# fcu.net
KiCad netlist of a schematic drawn in Altium Designer
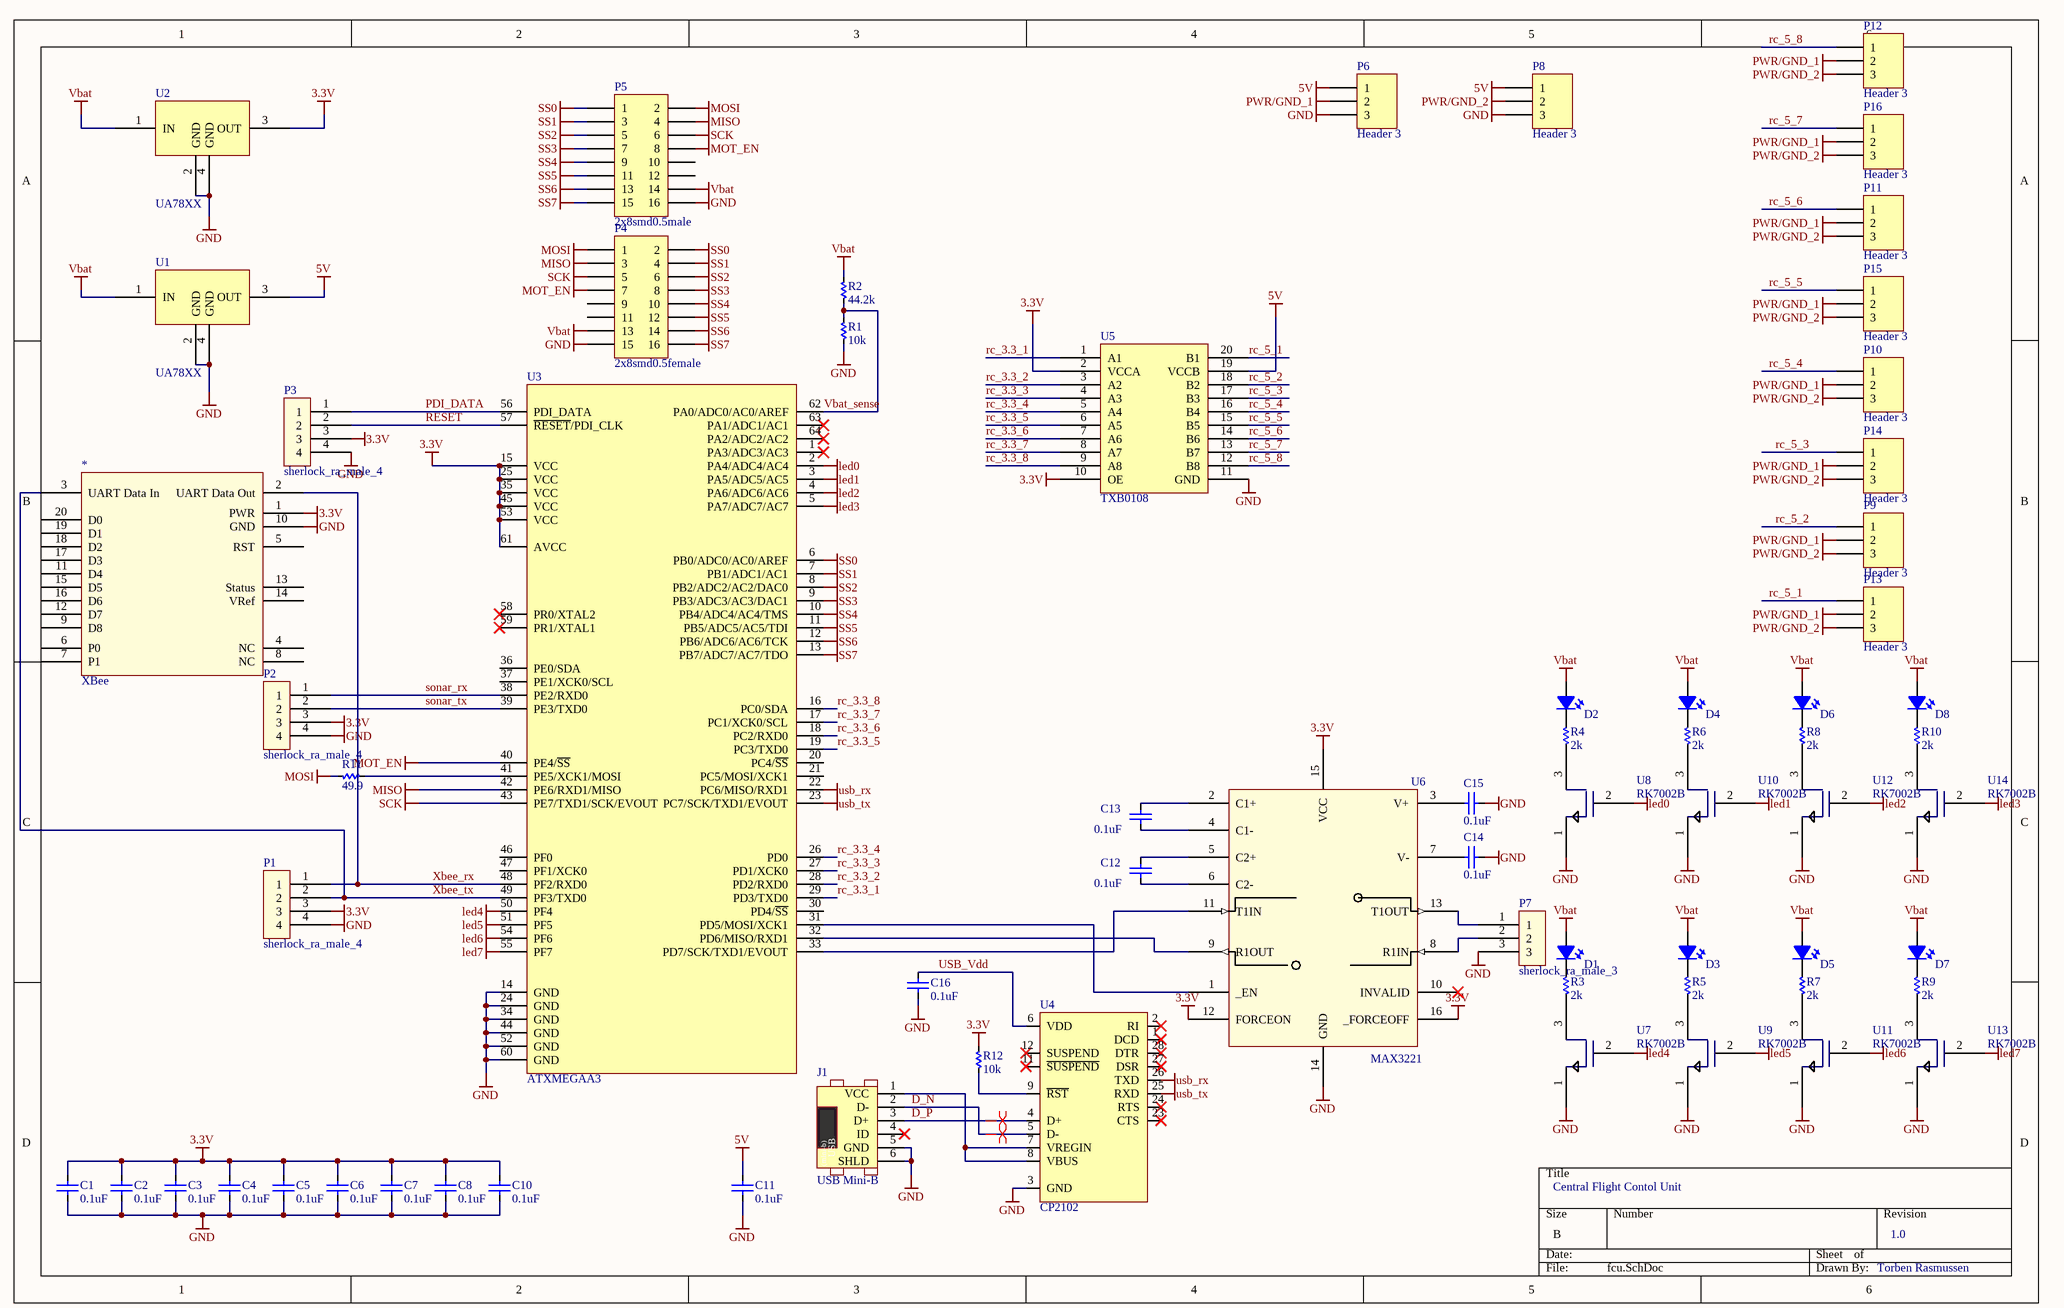
[diagram p0: fcu.SchDoc]

(export (version "E")
  (design (tool "Eeschema 10.0.6"))
  (components
    (comp (ref "*") (value "XBee") (footprint "XBee") (libsource (lib "fcu") (part "XBee")))
    (comp (ref "C1")
      (value "0.1uF")
      (footprint "0603 (1608) RECT")
      (fields
        (field (name "MANUFACTURER") "Murata")
        (field (name "PART NO.") "GRM188xxxxxxxxx")
        (field (name "Comment") "Capacitor")
      )
      (libsource (lib "SMT Chip") (part "Capacitor"))
    )
    (comp (ref "C2")
      (value "0.1uF")
      (footprint "0603 (1608) RECT")
      (fields
        (field (name "MANUFACTURER") "Murata")
        (field (name "PART NO.") "GRM188xxxxxxxxx")
        (field (name "Comment") "Capacitor")
      )
      (libsource (lib "SMT Chip") (part "Capacitor"))
    )
    (comp (ref "C3")
      (value "0.1uF")
      (footprint "0603 (1608) RECT")
      (fields
        (field (name "MANUFACTURER") "Murata")
        (field (name "PART NO.") "GRM188xxxxxxxxx")
        (field (name "Comment") "Capacitor")
      )
      (libsource (lib "SMT Chip") (part "Capacitor"))
    )
    (comp (ref "C4")
      (value "0.1uF")
      (footprint "0603 (1608) RECT")
      (fields
        (field (name "MANUFACTURER") "Murata")
        (field (name "PART NO.") "GRM188xxxxxxxxx")
        (field (name "Comment") "Capacitor")
      )
      (libsource (lib "SMT Chip") (part "Capacitor"))
    )
    (comp (ref "C5")
      (value "0.1uF")
      (footprint "0603 (1608) RECT")
      (fields
        (field (name "MANUFACTURER") "Murata")
        (field (name "PART NO.") "GRM188xxxxxxxxx")
        (field (name "Comment") "Capacitor")
      )
      (libsource (lib "SMT Chip") (part "Capacitor"))
    )
    (comp (ref "C6")
      (value "0.1uF")
      (footprint "0603 (1608) RECT")
      (fields
        (field (name "MANUFACTURER") "Murata")
        (field (name "PART NO.") "GRM188xxxxxxxxx")
        (field (name "Comment") "Capacitor")
      )
      (libsource (lib "SMT Chip") (part "Capacitor"))
    )
    (comp (ref "C7")
      (value "0.1uF")
      (footprint "0603 (1608) RECT")
      (fields
        (field (name "MANUFACTURER") "Murata")
        (field (name "PART NO.") "GRM188xxxxxxxxx")
        (field (name "Comment") "Capacitor")
      )
      (libsource (lib "SMT Chip") (part "Capacitor"))
    )
    (comp (ref "C8")
      (value "0.1uF")
      (footprint "0603 (1608) RECT")
      (fields
        (field (name "MANUFACTURER") "Murata")
        (field (name "PART NO.") "GRM188xxxxxxxxx")
        (field (name "Comment") "Capacitor")
      )
      (libsource (lib "SMT Chip") (part "Capacitor"))
    )
    (comp (ref "C10")
      (value "0.1uF")
      (footprint "0603 (1608) RECT")
      (fields
        (field (name "MANUFACTURER") "Murata")
        (field (name "PART NO.") "GRM188xxxxxxxxx")
        (field (name "Comment") "Capacitor")
      )
      (libsource (lib "SMT Chip") (part "Capacitor"))
    )
    (comp (ref "C11")
      (value "0.1uF")
      (footprint "0603 (1608) RECT")
      (fields
        (field (name "MANUFACTURER") "Murata")
        (field (name "PART NO.") "GRM188xxxxxxxxx")
        (field (name "Comment") "Capacitor")
      )
      (libsource (lib "SMT Chip") (part "Capacitor"))
    )
    (comp (ref "C12")
      (value "0.1uF")
      (footprint "0603 (1608) RECT")
      (fields
        (field (name "MANUFACTURER") "Murata")
        (field (name "PART NO.") "GRM188xxxxxxxxx")
        (field (name "Comment") "Capacitor")
      )
      (libsource (lib "SMT Chip") (part "Capacitor"))
    )
    (comp (ref "C13")
      (value "0.1uF")
      (footprint "0603 (1608) RECT")
      (fields
        (field (name "MANUFACTURER") "Murata")
        (field (name "PART NO.") "GRM188xxxxxxxxx")
        (field (name "Comment") "Capacitor")
      )
      (libsource (lib "SMT Chip") (part "Capacitor"))
    )
    (comp (ref "C14")
      (value "0.1uF")
      (footprint "0603 (1608) RECT")
      (fields
        (field (name "MANUFACTURER") "Murata")
        (field (name "PART NO.") "GRM188xxxxxxxxx")
        (field (name "Comment") "Capacitor")
      )
      (libsource (lib "SMT Chip") (part "Capacitor"))
    )
    (comp (ref "C15")
      (value "0.1uF")
      (footprint "0603 (1608) RECT")
      (fields
        (field (name "MANUFACTURER") "Murata")
        (field (name "PART NO.") "GRM188xxxxxxxxx")
        (field (name "Comment") "Capacitor")
      )
      (libsource (lib "SMT Chip") (part "Capacitor"))
    )
    (comp (ref "C16")
      (value "0.1uF")
      (footprint "0603 (1608) RECT")
      (fields
        (field (name "MANUFACTURER") "Murata")
        (field (name "PART NO.") "GRM188xxxxxxxxx")
        (field (name "Comment") "Capacitor")
      )
      (libsource (lib "SMT Chip") (part "Capacitor"))
    )
    (comp (ref "D1")
      (value "LED")
      (footprint "LED 0603 (1608)")
      (fields (field (name "PART NO.") "LTST-C170XXX") (field (name "MANUFACTURER") "Lite-On"))
      (libsource (lib "Diode") (part "LED"))
    )
    (comp (ref "D2")
      (value "LED")
      (footprint "LED 0603 (1608)")
      (fields (field (name "PART NO.") "LTST-C170XXX") (field (name "MANUFACTURER") "Lite-On"))
      (libsource (lib "Diode") (part "LED"))
    )
    (comp (ref "D3")
      (value "LED")
      (footprint "LED 0603 (1608)")
      (fields (field (name "PART NO.") "LTST-C170XXX") (field (name "MANUFACTURER") "Lite-On"))
      (libsource (lib "Diode") (part "LED"))
    )
    (comp (ref "D4")
      (value "LED")
      (footprint "LED 0603 (1608)")
      (fields (field (name "PART NO.") "LTST-C170XXX") (field (name "MANUFACTURER") "Lite-On"))
      (libsource (lib "Diode") (part "LED"))
    )
    (comp (ref "D5")
      (value "LED")
      (footprint "LED 0603 (1608)")
      (fields (field (name "PART NO.") "LTST-C170XXX") (field (name "MANUFACTURER") "Lite-On"))
      (libsource (lib "Diode") (part "LED"))
    )
    (comp (ref "D6")
      (value "LED")
      (footprint "LED 0603 (1608)")
      (fields (field (name "PART NO.") "LTST-C170XXX") (field (name "MANUFACTURER") "Lite-On"))
      (libsource (lib "Diode") (part "LED"))
    )
    (comp (ref "D7")
      (value "LED")
      (footprint "LED 0603 (1608)")
      (fields (field (name "PART NO.") "LTST-C170XXX") (field (name "MANUFACTURER") "Lite-On"))
      (libsource (lib "Diode") (part "LED"))
    )
    (comp (ref "D8")
      (value "LED")
      (footprint "LED 0603 (1608)")
      (fields (field (name "PART NO.") "LTST-C170XXX") (field (name "MANUFACTURER") "Lite-On"))
      (libsource (lib "Diode") (part "LED"))
    )
    (comp (ref "J1")
      (value "USB Mini-B")
      (footprint "USB MINI-B (PCB TAB)")
      (fields (field (name "PART NO.") "54819-0572") (field (name "MANUFACTURER") "Molex"))
      (libsource (lib "USB") (part "USB Mini-B"))
    )
    (comp (ref "P1")
      (value "sherlock_ra_male_4")
      (footprint "sherlock_ra_male_4")
      (libsource (lib "fcu") (part "sherlock_ra_male_4"))
    )
    (comp (ref "P2")
      (value "sherlock_ra_male_4")
      (footprint "sherlock_ra_male_4")
      (libsource (lib "fcu") (part "sherlock_ra_male_4"))
    )
    (comp (ref "P3")
      (value "sherlock_ra_male_4")
      (footprint "sherlock_ra_male_4")
      (libsource (lib "fcu") (part "sherlock_ra_male_4"))
    )
    (comp (ref "P4")
      (value "2x8smd0.5female")
      (footprint "S9007E-08-ND")
      (fields (field (name "PART NO.") "S9007E-08-ND"))
      (libsource (lib "falcon_mcu") (part "2x8smd0.5female"))
    )
    (comp (ref "P5")
      (value "2x8smd0.5male")
      (footprint "S9007E-08-ND-noholes")
      (fields (field (name "PART NO.") "S9013E-08-ND"))
      (libsource (lib "falcon_mcu") (part "2x8smd0.5male"))
    )
    (comp (ref "P6")
      (value "Header 3")
      (footprint "HDR1X3")
      (description "Header, 3-Pin")
      (fields (field (name "PUBLISHER") "Altium Limited"))
      (libsource (lib "Miscellaneous Connectors") (part "Header 3"))
    )
    (comp (ref "P7")
      (value "sherlock_ra_male_3")
      (footprint "sherlock_ra_male_3")
      (libsource (lib "fcu") (part "sherlock_ra_male_3"))
    )
    (comp (ref "P8")
      (value "Header 3")
      (footprint "HDR1X3")
      (description "Header, 3-Pin")
      (fields (field (name "PUBLISHER") "Altium Limited"))
      (libsource (lib "Miscellaneous Connectors") (part "Header 3"))
    )
    (comp (ref "P9")
      (value "Header 3")
      (footprint "HDR1X3")
      (description "Header, 3-Pin")
      (fields (field (name "PUBLISHER") "Altium Limited"))
      (libsource (lib "Miscellaneous Connectors") (part "Header 3"))
    )
    (comp (ref "P10")
      (value "Header 3")
      (footprint "HDR1X3")
      (description "Header, 3-Pin")
      (fields (field (name "PUBLISHER") "Altium Limited"))
      (libsource (lib "Miscellaneous Connectors") (part "Header 3"))
    )
    (comp (ref "P11")
      (value "Header 3")
      (footprint "HDR1X3")
      (description "Header, 3-Pin")
      (fields (field (name "PUBLISHER") "Altium Limited"))
      (libsource (lib "Miscellaneous Connectors") (part "Header 3"))
    )
    (comp (ref "P12")
      (value "Header 3")
      (footprint "HDR1X3")
      (description "Header, 3-Pin")
      (fields (field (name "PUBLISHER") "Altium Limited"))
      (libsource (lib "Miscellaneous Connectors") (part "Header 3"))
    )
    (comp (ref "P13")
      (value "Header 3")
      (footprint "HDR1X3")
      (description "Header, 3-Pin")
      (fields (field (name "PUBLISHER") "Altium Limited"))
      (libsource (lib "Miscellaneous Connectors") (part "Header 3"))
    )
    (comp (ref "P14")
      (value "Header 3")
      (footprint "HDR1X3")
      (description "Header, 3-Pin")
      (fields (field (name "PUBLISHER") "Altium Limited"))
      (libsource (lib "Miscellaneous Connectors") (part "Header 3"))
    )
    (comp (ref "P15")
      (value "Header 3")
      (footprint "HDR1X3")
      (description "Header, 3-Pin")
      (fields (field (name "PUBLISHER") "Altium Limited"))
      (libsource (lib "Miscellaneous Connectors") (part "Header 3"))
    )
    (comp (ref "P16")
      (value "Header 3")
      (footprint "HDR1X3")
      (description "Header, 3-Pin")
      (fields (field (name "PUBLISHER") "Altium Limited"))
      (libsource (lib "Miscellaneous Connectors") (part "Header 3"))
    )
    (comp (ref "R1")
      (value "10k")
      (footprint "0603 (1608) BRACKET")
      (description "Resistor")
      (fields
        (field (name "PART NO.") "CRCW06031K00xxxxxxxxxx")
        (field (name "MANUFACTURER") "Vishay / Dale")
      )
      (libsource (lib "SMT Chip") (part "Resistor"))
    )
    (comp (ref "R2")
      (value "44.2k")
      (footprint "0603 (1608) BRACKET")
      (description "Resistor")
      (fields
        (field (name "PART NO.") "CRCW06031K00xxxxxxxxxx")
        (field (name "MANUFACTURER") "Vishay / Dale")
      )
      (libsource (lib "SMT Chip") (part "Resistor"))
    )
    (comp (ref "R3")
      (value "2k")
      (footprint "0603 (1608) BRACKET")
      (description "Resistor")
      (fields
        (field (name "PART NO.") "CRCW06031K00xxxxxxxxxx")
        (field (name "MANUFACTURER") "Vishay / Dale")
      )
      (libsource (lib "SMT Chip") (part "Resistor"))
    )
    (comp (ref "R4")
      (value "2k")
      (footprint "0603 (1608) BRACKET")
      (description "Resistor")
      (fields
        (field (name "PART NO.") "CRCW06031K00xxxxxxxxxx")
        (field (name "MANUFACTURER") "Vishay / Dale")
      )
      (libsource (lib "SMT Chip") (part "Resistor"))
    )
    (comp (ref "R5")
      (value "2k")
      (footprint "0603 (1608) BRACKET")
      (description "Resistor")
      (fields
        (field (name "PART NO.") "CRCW06031K00xxxxxxxxxx")
        (field (name "MANUFACTURER") "Vishay / Dale")
      )
      (libsource (lib "SMT Chip") (part "Resistor"))
    )
    (comp (ref "R6")
      (value "2k")
      (footprint "0603 (1608) BRACKET")
      (description "Resistor")
      (fields
        (field (name "PART NO.") "CRCW06031K00xxxxxxxxxx")
        (field (name "MANUFACTURER") "Vishay / Dale")
      )
      (libsource (lib "SMT Chip") (part "Resistor"))
    )
    (comp (ref "R7")
      (value "2k")
      (footprint "0603 (1608) BRACKET")
      (description "Resistor")
      (fields
        (field (name "PART NO.") "CRCW06031K00xxxxxxxxxx")
        (field (name "MANUFACTURER") "Vishay / Dale")
      )
      (libsource (lib "SMT Chip") (part "Resistor"))
    )
    (comp (ref "R8")
      (value "2k")
      (footprint "0603 (1608) BRACKET")
      (description "Resistor")
      (fields
        (field (name "PART NO.") "CRCW06031K00xxxxxxxxxx")
        (field (name "MANUFACTURER") "Vishay / Dale")
      )
      (libsource (lib "SMT Chip") (part "Resistor"))
    )
    (comp (ref "R9")
      (value "2k")
      (footprint "0603 (1608) BRACKET")
      (description "Resistor")
      (fields
        (field (name "PART NO.") "CRCW06031K00xxxxxxxxxx")
        (field (name "MANUFACTURER") "Vishay / Dale")
      )
      (libsource (lib "SMT Chip") (part "Resistor"))
    )
    (comp (ref "R10")
      (value "2k")
      (footprint "0603 (1608) BRACKET")
      (description "Resistor")
      (fields
        (field (name "PART NO.") "CRCW06031K00xxxxxxxxxx")
        (field (name "MANUFACTURER") "Vishay / Dale")
      )
      (libsource (lib "SMT Chip") (part "Resistor"))
    )
    (comp (ref "R11")
      (value "49.9")
      (footprint "0603 (1608) BRACKET")
      (description "Resistor")
      (fields
        (field (name "PART NO.") "CRCW06031K00xxxxxxxxxx")
        (field (name "MANUFACTURER") "Vishay / Dale")
      )
      (libsource (lib "SMT Chip") (part "Resistor"))
    )
    (comp (ref "R12")
      (value "10k")
      (footprint "0603 (1608) BRACKET")
      (description "Resistor")
      (fields
        (field (name "PART NO.") "CRCW06031K00xxxxxxxxxx")
        (field (name "MANUFACTURER") "Vishay / Dale")
      )
      (libsource (lib "SMT Chip") (part "Resistor"))
    )
    (comp (ref "U1") (value "UA78XX") (footprint "SOT-223") (libsource (lib "fcu") (part "UA78XX")))
    (comp (ref "U2") (value "UA78XX") (footprint "SOT-223") (libsource (lib "fcu") (part "UA78XX")))
    (comp (ref "U3")
      (value "ATXMEGAA3")
      (footprint "QFN-64")
      (fields (field (name "MANUFACTURER") "Atmel") (field (name "PART NO.") "ATXMEGA128A3"))
      (libsource (lib "XMEGA") (part "ATXMEGAA3"))
    )
    (comp (ref "U4")
      (value "CP2102")
      (footprint "QFN28 5x5 SILABS")
      (fields (field (name "MANUFACTURER") "Silicon Labs"))
      (libsource (lib "CP2102") (part "CP2102"))
    )
    (comp (ref "U5")
      (value "TXB0108")
      (footprint "falcon:TSSOP-20")
      (fields (field (name "MANUFACTURER") "Texas Instruments"))
      (libsource (lib "TXB0108") (part "TXB0108"))
    )
    (comp (ref "U6") (value "MAX3221") (footprint "TSSOP-16") (libsource (lib "fcu") (part "MAX3221")))
    (comp (ref "U7") (value "RK7002B") (footprint "SOT-23-RK7002B") (libsource (lib "fcu") (part "RK7002B")))
    (comp (ref "U8") (value "RK7002B") (footprint "SOT-23-RK7002B") (libsource (lib "fcu") (part "RK7002B")))
    (comp (ref "U9") (value "RK7002B") (footprint "SOT-23-RK7002B") (libsource (lib "fcu") (part "RK7002B")))
    (comp (ref "U10") (value "RK7002B") (footprint "SOT-23-RK7002B") (libsource (lib "fcu") (part "RK7002B")))
    (comp (ref "U11") (value "RK7002B") (footprint "SOT-23-RK7002B") (libsource (lib "fcu") (part "RK7002B")))
    (comp (ref "U12") (value "RK7002B") (footprint "SOT-23-RK7002B") (libsource (lib "fcu") (part "RK7002B")))
    (comp (ref "U13") (value "RK7002B") (footprint "SOT-23-RK7002B") (libsource (lib "fcu") (part "RK7002B")))
    (comp (ref "U14") (value "RK7002B") (footprint "SOT-23-RK7002B") (libsource (lib "fcu") (part "RK7002B")))
  )
  (nets
    (net (code "1") (name "/D_N") (class "Default")
      (node (ref "J1") (pin "2") (pinfunction "D-_2") (pintype "passive"))
      (node (ref "U4") (pin "5") (pinfunction "D-_5") (pintype "passive"))
    )
    (net (code "2") (name "/D_P") (class "Default")
      (node (ref "J1") (pin "3") (pinfunction "D+_3") (pintype "passive"))
      (node (ref "U4") (pin "4") (pinfunction "D+_4") (pintype "passive"))
    )
    (net (code "3") (name "/PDI_DATA") (class "Default")
      (node (ref "P3") (pin "1") (pinfunction "1_1") (pintype "passive"))
      (node (ref "U3") (pin "56") (pinfunction "PDI_DATA_56") (pintype "passive"))
    )
    (net (code "4") (name "/RESET") (class "Default")
      (node (ref "P3") (pin "2") (pinfunction "2_2") (pintype "passive"))
      (node (ref "U3") (pin "57") (pinfunction "~{RESET}/PDI_CLK_57") (pintype "passive"))
    )
    (net (code "5") (name "/USB_Vdd") (class "Default")
      (node (ref "C16") (pin "1") (pinfunction "1_1") (pintype "passive"))
      (node (ref "U4") (pin "6") (pinfunction "VDD_6") (pintype "passive"))
    )
    (net (code "6") (name "/Vbat_sense") (class "Default")
      (node (ref "R1") (pin "2") (pinfunction "2_2") (pintype "passive"))
      (node (ref "R2") (pin "1") (pinfunction "1_1") (pintype "passive"))
      (node (ref "U3") (pin "62") (pinfunction "PA0/ADC0/AC0/AREF_62") (pintype "passive"))
    )
    (net (code "7") (name "/Xbee_rx") (class "Default")
      (node (ref "*") (pin "2") (pinfunction "UART_Data_Out_2") (pintype "passive"))
      (node (ref "P1") (pin "1") (pinfunction "1_1") (pintype "passive"))
      (node (ref "U3") (pin "48") (pinfunction "PF2/RXD0_48") (pintype "passive"))
    )
    (net (code "8") (name "/Xbee_tx") (class "Default")
      (node (ref "*") (pin "3") (pinfunction "UART_Data_In_3") (pintype "passive"))
      (node (ref "P1") (pin "2") (pinfunction "2_2") (pintype "passive"))
      (node (ref "U3") (pin "49") (pinfunction "PF3/TXD0_49") (pintype "passive"))
    )
    (net (code "9") (name "/rc_3.3_1") (class "Default")
      (node (ref "U3") (pin "29") (pinfunction "PD3/TXD0_29") (pintype "passive"))
      (node (ref "U5") (pin "1") (pinfunction "A1_1") (pintype "passive"))
    )
    (net (code "10") (name "/rc_3.3_2") (class "Default")
      (node (ref "U3") (pin "28") (pinfunction "PD2/RXD0_28") (pintype "passive"))
      (node (ref "U5") (pin "3") (pinfunction "A2_3") (pintype "passive"))
    )
    (net (code "11") (name "/rc_3.3_3") (class "Default")
      (node (ref "U3") (pin "27") (pinfunction "PD1/XCK0_27") (pintype "passive"))
      (node (ref "U5") (pin "4") (pinfunction "A3_4") (pintype "passive"))
    )
    (net (code "12") (name "/rc_3.3_4") (class "Default")
      (node (ref "U3") (pin "26") (pinfunction "PD0_26") (pintype "passive"))
      (node (ref "U5") (pin "5") (pinfunction "A4_5") (pintype "passive"))
    )
    (net (code "13") (name "/rc_3.3_5") (class "Default")
      (node (ref "U3") (pin "19") (pinfunction "PC3/TXD0_19") (pintype "passive"))
      (node (ref "U5") (pin "6") (pinfunction "A5_6") (pintype "passive"))
    )
    (net (code "14") (name "/rc_3.3_6") (class "Default")
      (node (ref "U3") (pin "18") (pinfunction "PC2/RXD0_18") (pintype "passive"))
      (node (ref "U5") (pin "7") (pinfunction "A6_7") (pintype "passive"))
    )
    (net (code "15") (name "/rc_3.3_7") (class "Default")
      (node (ref "U3") (pin "17") (pinfunction "PC1/XCK0/SCL_17") (pintype "passive"))
      (node (ref "U5") (pin "8") (pinfunction "A7_8") (pintype "passive"))
    )
    (net (code "16") (name "/rc_3.3_8") (class "Default")
      (node (ref "U3") (pin "16") (pinfunction "PC0/SDA_16") (pintype "passive"))
      (node (ref "U5") (pin "9") (pinfunction "A8_9") (pintype "passive"))
    )
    (net (code "17") (name "/rc_5_1") (class "Default")
      (node (ref "P13") (pin "1") (pinfunction "1_1") (pintype "passive"))
      (node (ref "U5") (pin "20") (pinfunction "B1_20") (pintype "passive"))
    )
    (net (code "18") (name "/rc_5_2") (class "Default")
      (node (ref "P9") (pin "1") (pinfunction "1_1") (pintype "passive"))
      (node (ref "U5") (pin "18") (pinfunction "B2_18") (pintype "passive"))
    )
    (net (code "19") (name "/rc_5_3") (class "Default")
      (node (ref "P14") (pin "1") (pinfunction "1_1") (pintype "passive"))
      (node (ref "U5") (pin "17") (pinfunction "B3_17") (pintype "passive"))
    )
    (net (code "20") (name "/rc_5_4") (class "Default")
      (node (ref "P10") (pin "1") (pinfunction "1_1") (pintype "passive"))
      (node (ref "U5") (pin "16") (pinfunction "B4_16") (pintype "passive"))
    )
    (net (code "21") (name "/rc_5_5") (class "Default")
      (node (ref "P15") (pin "1") (pinfunction "1_1") (pintype "passive"))
      (node (ref "U5") (pin "15") (pinfunction "B5_15") (pintype "passive"))
    )
    (net (code "22") (name "/rc_5_6") (class "Default")
      (node (ref "P11") (pin "1") (pinfunction "1_1") (pintype "passive"))
      (node (ref "U5") (pin "14") (pinfunction "B6_14") (pintype "passive"))
    )
    (net (code "23") (name "/rc_5_7") (class "Default")
      (node (ref "P16") (pin "1") (pinfunction "1_1") (pintype "passive"))
      (node (ref "U5") (pin "13") (pinfunction "B7_13") (pintype "passive"))
    )
    (net (code "24") (name "/rc_5_8") (class "Default")
      (node (ref "P12") (pin "1") (pinfunction "1_1") (pintype "passive"))
      (node (ref "U5") (pin "12") (pinfunction "B8_12") (pintype "passive"))
    )
    (net (code "25") (name "/sonar_rx") (class "Default")
      (node (ref "P2") (pin "1") (pinfunction "1_1") (pintype "passive"))
      (node (ref "U3") (pin "38") (pinfunction "PE2/RXD0_38") (pintype "passive"))
    )
    (net (code "26") (name "/sonar_tx") (class "Default")
      (node (ref "P2") (pin "2") (pinfunction "2_2") (pintype "passive"))
      (node (ref "U3") (pin "39") (pinfunction "PE3/TXD0_39") (pintype "passive"))
    )
    (net (code "27") (name "3.3V") (class "Default")
      (node (ref "*") (pin "1") (pinfunction "PWR_1") (pintype "passive"))
      (node (ref "C1") (pin "1") (pinfunction "1_1") (pintype "passive"))
      (node (ref "C10") (pin "1") (pinfunction "1_1") (pintype "passive"))
      (node (ref "C2") (pin "1") (pinfunction "1_1") (pintype "passive"))
      (node (ref "C3") (pin "1") (pinfunction "1_1") (pintype "passive"))
      (node (ref "C4") (pin "1") (pinfunction "1_1") (pintype "passive"))
      (node (ref "C5") (pin "1") (pinfunction "1_1") (pintype "passive"))
      (node (ref "C6") (pin "1") (pinfunction "1_1") (pintype "passive"))
      (node (ref "C7") (pin "1") (pinfunction "1_1") (pintype "passive"))
      (node (ref "C8") (pin "1") (pinfunction "1_1") (pintype "passive"))
      (node (ref "P1") (pin "3") (pinfunction "3_3") (pintype "passive"))
      (node (ref "P2") (pin "3") (pinfunction "3_3") (pintype "passive"))
      (node (ref "P3") (pin "3") (pinfunction "3_3") (pintype "passive"))
      (node (ref "R12") (pin "1") (pinfunction "1_1") (pintype "passive"))
      (node (ref "U2") (pin "3") (pinfunction "OUT_3") (pintype "passive"))
      (node (ref "U3") (pin "15") (pinfunction "VCC_15") (pintype "passive"))
      (node (ref "U3") (pin "25") (pinfunction "VCC_25") (pintype "passive"))
      (node (ref "U3") (pin "35") (pinfunction "VCC_35") (pintype "passive"))
      (node (ref "U3") (pin "45") (pinfunction "VCC_45") (pintype "passive"))
      (node (ref "U3") (pin "53") (pinfunction "VCC_53") (pintype "passive"))
      (node (ref "U3") (pin "61") (pinfunction "AVCC_61") (pintype "passive"))
      (node (ref "U5") (pin "10") (pinfunction "OE_10") (pintype "passive"))
      (node (ref "U5") (pin "2") (pinfunction "VCCA_2") (pintype "power_in"))
      (node (ref "U6") (pin "12") (pinfunction "FORCEON_12") (pintype "passive"))
      (node (ref "U6") (pin "15") (pinfunction "VCC_15") (pintype "passive"))
      (node (ref "U6") (pin "16") (pinfunction "_FORCEOFF_16") (pintype "passive"))
    )
    (net (code "28") (name "5V") (class "Default")
      (node (ref "C11") (pin "1") (pinfunction "1_1") (pintype "passive"))
      (node (ref "P6") (pin "1") (pinfunction "1_1") (pintype "passive"))
      (node (ref "P8") (pin "1") (pinfunction "1_1") (pintype "passive"))
      (node (ref "U1") (pin "3") (pinfunction "OUT_3") (pintype "passive"))
      (node (ref "U5") (pin "19") (pinfunction "VCCB_19") (pintype "power_in"))
    )
    (net (code "29") (name "GND") (class "Default")
      (node (ref "*") (pin "10") (pinfunction "GND_10") (pintype "passive"))
      (node (ref "C1") (pin "2") (pinfunction "2_2") (pintype "passive"))
      (node (ref "C10") (pin "2") (pinfunction "2_2") (pintype "passive"))
      (node (ref "C11") (pin "2") (pinfunction "2_2") (pintype "passive"))
      (node (ref "C14") (pin "2") (pinfunction "2_2") (pintype "passive"))
      (node (ref "C15") (pin "2") (pinfunction "2_2") (pintype "passive"))
      (node (ref "C16") (pin "2") (pinfunction "2_2") (pintype "passive"))
      (node (ref "C2") (pin "2") (pinfunction "2_2") (pintype "passive"))
      (node (ref "C3") (pin "2") (pinfunction "2_2") (pintype "passive"))
      (node (ref "C4") (pin "2") (pinfunction "2_2") (pintype "passive"))
      (node (ref "C5") (pin "2") (pinfunction "2_2") (pintype "passive"))
      (node (ref "C6") (pin "2") (pinfunction "2_2") (pintype "passive"))
      (node (ref "C7") (pin "2") (pinfunction "2_2") (pintype "passive"))
      (node (ref "C8") (pin "2") (pinfunction "2_2") (pintype "passive"))
      (node (ref "J1") (pin "5") (pinfunction "GND_5") (pintype "passive"))
      (node (ref "J1") (pin "6") (pinfunction "SHLD_6") (pintype "passive"))
      (node (ref "P1") (pin "4") (pinfunction "4_4") (pintype "passive"))
      (node (ref "P2") (pin "4") (pinfunction "4_4") (pintype "passive"))
      (node (ref "P3") (pin "4") (pinfunction "4_4") (pintype "passive"))
      (node (ref "P4") (pin "15") (pinfunction "15_15") (pintype "passive"))
      (node (ref "P5") (pin "16") (pinfunction "16_16") (pintype "passive"))
      (node (ref "P6") (pin "3") (pinfunction "3_3") (pintype "passive"))
      (node (ref "P7") (pin "3") (pinfunction "3_3") (pintype "passive"))
      (node (ref "P8") (pin "3") (pinfunction "3_3") (pintype "passive"))
      (node (ref "R1") (pin "1") (pinfunction "1_1") (pintype "passive"))
      (node (ref "U1") (pin "2") (pinfunction "GND_2") (pintype "passive"))
      (node (ref "U1") (pin "4") (pinfunction "GND_4") (pintype "passive"))
      (node (ref "U10") (pin "1") (pinfunction "S_1") (pintype "passive"))
      (node (ref "U11") (pin "1") (pinfunction "S_1") (pintype "passive"))
      (node (ref "U12") (pin "1") (pinfunction "S_1") (pintype "passive"))
      (node (ref "U13") (pin "1") (pinfunction "S_1") (pintype "passive"))
      (node (ref "U14") (pin "1") (pinfunction "S_1") (pintype "passive"))
      (node (ref "U2") (pin "2") (pinfunction "GND_2") (pintype "passive"))
      (node (ref "U2") (pin "4") (pinfunction "GND_4") (pintype "passive"))
      (node (ref "U3") (pin "14") (pinfunction "GND_14") (pintype "passive"))
      (node (ref "U3") (pin "24") (pinfunction "GND_24") (pintype "passive"))
      (node (ref "U3") (pin "34") (pinfunction "GND_34") (pintype "passive"))
      (node (ref "U3") (pin "44") (pinfunction "GND_44") (pintype "passive"))
      (node (ref "U3") (pin "52") (pinfunction "GND_52") (pintype "passive"))
      (node (ref "U3") (pin "60") (pinfunction "GND_60") (pintype "passive"))
      (node (ref "U4") (pin "3") (pinfunction "GND_3") (pintype "passive"))
      (node (ref "U5") (pin "11") (pinfunction "GND_11") (pintype "power_in"))
      (node (ref "U6") (pin "14") (pinfunction "GND_14") (pintype "passive"))
      (node (ref "U7") (pin "1") (pinfunction "S_1") (pintype "passive"))
      (node (ref "U8") (pin "1") (pinfunction "S_1") (pintype "passive"))
      (node (ref "U9") (pin "1") (pinfunction "S_1") (pintype "passive"))
    )
    (net (code "30") (name "MISO") (class "Default")
      (node (ref "P4") (pin "3") (pinfunction "3_3") (pintype "passive"))
      (node (ref "P5") (pin "4") (pinfunction "4_4") (pintype "passive"))
      (node (ref "U3") (pin "42") (pinfunction "PE6/RXD1/MISO_42") (pintype "passive"))
    )
    (net (code "31") (name "MOSI") (class "Default")
      (node (ref "P4") (pin "1") (pinfunction "1_1") (pintype "passive"))
      (node (ref "P5") (pin "2") (pinfunction "2_2") (pintype "passive"))
      (node (ref "R11") (pin "2") (pinfunction "2_2") (pintype "passive"))
    )
    (net (code "32") (name "MOT_EN") (class "Default")
      (node (ref "P4") (pin "7") (pinfunction "7_7") (pintype "passive"))
      (node (ref "P5") (pin "8") (pinfunction "8_8") (pintype "passive"))
      (node (ref "U3") (pin "40") (pinfunction "PE4/~{SS}_40") (pintype "passive"))
    )
    (net (code "33") (name "Net-(D1-Pad2)") (class "Default")
      (node (ref "D1") (pin "2") (pinfunction "2_2") (pintype "passive"))
      (node (ref "R3") (pin "1") (pinfunction "1_1") (pintype "passive"))
    )
    (net (code "34") (name "Net-(D2-Pad2)") (class "Default")
      (node (ref "D2") (pin "2") (pinfunction "2_2") (pintype "passive"))
      (node (ref "R4") (pin "1") (pinfunction "1_1") (pintype "passive"))
    )
    (net (code "35") (name "Net-(D3-Pad2)") (class "Default")
      (node (ref "D3") (pin "2") (pinfunction "2_2") (pintype "passive"))
      (node (ref "R5") (pin "1") (pinfunction "1_1") (pintype "passive"))
    )
    (net (code "36") (name "Net-(D4-Pad2)") (class "Default")
      (node (ref "D4") (pin "2") (pinfunction "2_2") (pintype "passive"))
      (node (ref "R6") (pin "1") (pinfunction "1_1") (pintype "passive"))
    )
    (net (code "37") (name "Net-(D5-Pad2)") (class "Default")
      (node (ref "D5") (pin "2") (pinfunction "2_2") (pintype "passive"))
      (node (ref "R7") (pin "1") (pinfunction "1_1") (pintype "passive"))
    )
    (net (code "38") (name "Net-(D6-Pad2)") (class "Default")
      (node (ref "D6") (pin "2") (pinfunction "2_2") (pintype "passive"))
      (node (ref "R8") (pin "1") (pinfunction "1_1") (pintype "passive"))
    )
    (net (code "39") (name "Net-(D7-Pad2)") (class "Default")
      (node (ref "D7") (pin "2") (pinfunction "2_2") (pintype "passive"))
      (node (ref "R9") (pin "1") (pinfunction "1_1") (pintype "passive"))
    )
    (net (code "40") (name "Net-(D8-Pad2)") (class "Default")
      (node (ref "D8") (pin "2") (pinfunction "2_2") (pintype "passive"))
      (node (ref "R10") (pin "1") (pinfunction "1_1") (pintype "passive"))
    )
    (net (code "41") (name "Net-(J1-VCC)") (class "Default")
      (node (ref "J1") (pin "1") (pinfunction "VCC_1") (pintype "passive"))
      (node (ref "U4") (pin "7") (pinfunction "VREGIN_7") (pintype "passive"))
      (node (ref "U4") (pin "8") (pinfunction "VBUS_8") (pintype "passive"))
    )
    (net (code "42") (name "Net-(U3-PD5{slash}MOSI{slash}XCK1)") (class "Default")
      (node (ref "U3") (pin "31") (pinfunction "PD5/MOSI/XCK1_31") (pintype "passive"))
      (node (ref "U6") (pin "1") (pinfunction "_EN_1") (pintype "passive"))
    )
    (net (code "43") (name "Net-(U3-PD6{slash}MISO{slash}RXD1)") (class "Default")
      (node (ref "U3") (pin "32") (pinfunction "PD6/MISO/RXD1_32") (pintype "passive"))
      (node (ref "U6") (pin "9") (pinfunction "R1OUT_9") (pintype "output"))
    )
    (net (code "44") (name "Net-(U3-PD7{slash}SCK{slash}TXD1{slash}EVOUT)") (class "Default")
      (node (ref "U3") (pin "33") (pinfunction "PD7/SCK/TXD1/EVOUT_33") (pintype "passive"))
      (node (ref "U6") (pin "11") (pinfunction "T1IN_11") (pintype "input"))
    )
    (net (code "45") (name "Net-(U3-PE5{slash}XCK1{slash}MOSI)") (class "Default")
      (node (ref "R11") (pin "1") (pinfunction "1_1") (pintype "passive"))
      (node (ref "U3") (pin "41") (pinfunction "PE5/XCK1/MOSI_41") (pintype "passive"))
    )
    (net (code "46") (name "Net-(U4-~{RST})") (class "Default")
      (node (ref "R12") (pin "2") (pinfunction "2_2") (pintype "passive"))
      (node (ref "U4") (pin "9") (pinfunction "~{RST}_9") (pintype "passive"))
    )
    (net (code "47") (name "Net-(U6-C1+)") (class "Default")
      (node (ref "C13") (pin "1") (pinfunction "1_1") (pintype "passive"))
      (node (ref "U6") (pin "2") (pinfunction "C1+_2") (pintype "passive"))
    )
    (net (code "48") (name "Net-(U6-C1-)") (class "Default")
      (node (ref "C13") (pin "2") (pinfunction "2_2") (pintype "passive"))
      (node (ref "U6") (pin "4") (pinfunction "C1-_4") (pintype "passive"))
    )
    (net (code "49") (name "Net-(U6-C2+)") (class "Default")
      (node (ref "C12") (pin "2") (pinfunction "2_2") (pintype "passive"))
      (node (ref "U6") (pin "5") (pinfunction "C2+_5") (pintype "passive"))
    )
    (net (code "50") (name "Net-(U6-C2-)") (class "Default")
      (node (ref "C12") (pin "1") (pinfunction "1_1") (pintype "passive"))
      (node (ref "U6") (pin "6") (pinfunction "C2-_6") (pintype "passive"))
    )
    (net (code "51") (name "Net-(U6-R1IN)") (class "Default")
      (node (ref "P7") (pin "2") (pinfunction "2_2") (pintype "passive"))
      (node (ref "U6") (pin "8") (pinfunction "R1IN_8") (pintype "input"))
    )
    (net (code "52") (name "Net-(U6-T1OUT)") (class "Default")
      (node (ref "P7") (pin "1") (pinfunction "1_1") (pintype "passive"))
      (node (ref "U6") (pin "13") (pinfunction "T1OUT_13") (pintype "output"))
    )
    (net (code "53") (name "Net-(U6-V+)") (class "Default")
      (node (ref "C15") (pin "1") (pinfunction "1_1") (pintype "passive"))
      (node (ref "U6") (pin "3") (pinfunction "V+_3") (pintype "passive"))
    )
    (net (code "54") (name "Net-(U6-V-)") (class "Default")
      (node (ref "C14") (pin "1") (pinfunction "1_1") (pintype "passive"))
      (node (ref "U6") (pin "7") (pinfunction "V-_7") (pintype "passive"))
    )
    (net (code "55") (name "Net-(U7-D)") (class "Default")
      (node (ref "R3") (pin "2") (pinfunction "2_2") (pintype "passive"))
      (node (ref "U7") (pin "3") (pinfunction "D_3") (pintype "passive"))
    )
    (net (code "56") (name "Net-(U8-D)") (class "Default")
      (node (ref "R4") (pin "2") (pinfunction "2_2") (pintype "passive"))
      (node (ref "U8") (pin "3") (pinfunction "D_3") (pintype "passive"))
    )
    (net (code "57") (name "Net-(U9-D)") (class "Default")
      (node (ref "R5") (pin "2") (pinfunction "2_2") (pintype "passive"))
      (node (ref "U9") (pin "3") (pinfunction "D_3") (pintype "passive"))
    )
    (net (code "58") (name "Net-(U10-D)") (class "Default")
      (node (ref "R6") (pin "2") (pinfunction "2_2") (pintype "passive"))
      (node (ref "U10") (pin "3") (pinfunction "D_3") (pintype "passive"))
    )
    (net (code "59") (name "Net-(U11-D)") (class "Default")
      (node (ref "R7") (pin "2") (pinfunction "2_2") (pintype "passive"))
      (node (ref "U11") (pin "3") (pinfunction "D_3") (pintype "passive"))
    )
    (net (code "60") (name "Net-(U12-D)") (class "Default")
      (node (ref "R8") (pin "2") (pinfunction "2_2") (pintype "passive"))
      (node (ref "U12") (pin "3") (pinfunction "D_3") (pintype "passive"))
    )
    (net (code "61") (name "Net-(U13-D)") (class "Default")
      (node (ref "R9") (pin "2") (pinfunction "2_2") (pintype "passive"))
      (node (ref "U13") (pin "3") (pinfunction "D_3") (pintype "passive"))
    )
    (net (code "62") (name "Net-(U14-D)") (class "Default")
      (node (ref "R10") (pin "2") (pinfunction "2_2") (pintype "passive"))
      (node (ref "U14") (pin "3") (pinfunction "D_3") (pintype "passive"))
    )
    (net (code "63") (name "PWR{slash}GND_1") (class "Default")
      (node (ref "P10") (pin "2") (pinfunction "2_2") (pintype "passive"))
      (node (ref "P11") (pin "2") (pinfunction "2_2") (pintype "passive"))
      (node (ref "P12") (pin "2") (pinfunction "2_2") (pintype "passive"))
      (node (ref "P13") (pin "2") (pinfunction "2_2") (pintype "passive"))
      (node (ref "P14") (pin "2") (pinfunction "2_2") (pintype "passive"))
      (node (ref "P15") (pin "2") (pinfunction "2_2") (pintype "passive"))
      (node (ref "P16") (pin "2") (pinfunction "2_2") (pintype "passive"))
      (node (ref "P6") (pin "2") (pinfunction "2_2") (pintype "passive"))
      (node (ref "P9") (pin "2") (pinfunction "2_2") (pintype "passive"))
    )
    (net (code "64") (name "PWR{slash}GND_2") (class "Default")
      (node (ref "P10") (pin "3") (pinfunction "3_3") (pintype "passive"))
      (node (ref "P11") (pin "3") (pinfunction "3_3") (pintype "passive"))
      (node (ref "P12") (pin "3") (pinfunction "3_3") (pintype "passive"))
      (node (ref "P13") (pin "3") (pinfunction "3_3") (pintype "passive"))
      (node (ref "P14") (pin "3") (pinfunction "3_3") (pintype "passive"))
      (node (ref "P15") (pin "3") (pinfunction "3_3") (pintype "passive"))
      (node (ref "P16") (pin "3") (pinfunction "3_3") (pintype "passive"))
      (node (ref "P8") (pin "2") (pinfunction "2_2") (pintype "passive"))
      (node (ref "P9") (pin "3") (pinfunction "3_3") (pintype "passive"))
    )
    (net (code "65") (name "SCK") (class "Default")
      (node (ref "P4") (pin "5") (pinfunction "5_5") (pintype "passive"))
      (node (ref "P5") (pin "6") (pinfunction "6_6") (pintype "passive"))
      (node (ref "U3") (pin "43") (pinfunction "PE7/TXD1/SCK/EVOUT_43") (pintype "passive"))
    )
    (net (code "66") (name "SS0") (class "Default")
      (node (ref "P4") (pin "2") (pinfunction "2_2") (pintype "passive"))
      (node (ref "P5") (pin "1") (pinfunction "1_1") (pintype "passive"))
      (node (ref "U3") (pin "6") (pinfunction "PB0/ADC0/AC0/AREF_6") (pintype "passive"))
    )
    (net (code "67") (name "SS1") (class "Default")
      (node (ref "P4") (pin "4") (pinfunction "4_4") (pintype "passive"))
      (node (ref "P5") (pin "3") (pinfunction "3_3") (pintype "passive"))
      (node (ref "U3") (pin "7") (pinfunction "PB1/ADC1/AC1_7") (pintype "passive"))
    )
    (net (code "68") (name "SS2") (class "Default")
      (node (ref "P4") (pin "6") (pinfunction "6_6") (pintype "passive"))
      (node (ref "P5") (pin "5") (pinfunction "5_5") (pintype "passive"))
      (node (ref "U3") (pin "8") (pinfunction "PB2/ADC2/AC2/DAC0_8") (pintype "passive"))
    )
    (net (code "69") (name "SS3") (class "Default")
      (node (ref "P4") (pin "8") (pinfunction "8_8") (pintype "passive"))
      (node (ref "P5") (pin "7") (pinfunction "7_7") (pintype "passive"))
      (node (ref "U3") (pin "9") (pinfunction "PB3/ADC3/AC3/DAC1_9") (pintype "passive"))
    )
    (net (code "70") (name "SS4") (class "Default")
      (node (ref "P4") (pin "10") (pinfunction "10_10") (pintype "passive"))
      (node (ref "P5") (pin "9") (pinfunction "9_9") (pintype "passive"))
      (node (ref "U3") (pin "10") (pinfunction "PB4/ADC4/AC4/TMS_10") (pintype "passive"))
    )
    (net (code "71") (name "SS5") (class "Default")
      (node (ref "P4") (pin "12") (pinfunction "12_12") (pintype "passive"))
      (node (ref "P5") (pin "11") (pinfunction "11_11") (pintype "passive"))
      (node (ref "U3") (pin "11") (pinfunction "PB5/ADC5/AC5/TDI_11") (pintype "passive"))
    )
    (net (code "72") (name "SS6") (class "Default")
      (node (ref "P4") (pin "14") (pinfunction "14_14") (pintype "passive"))
      (node (ref "P5") (pin "13") (pinfunction "13_13") (pintype "passive"))
      (node (ref "U3") (pin "12") (pinfunction "PB6/ADC6/AC6/TCK_12") (pintype "passive"))
    )
    (net (code "73") (name "SS7") (class "Default")
      (node (ref "P4") (pin "16") (pinfunction "16_16") (pintype "passive"))
      (node (ref "P5") (pin "15") (pinfunction "15_15") (pintype "passive"))
      (node (ref "U3") (pin "13") (pinfunction "PB7/ADC7/AC7/TDO_13") (pintype "passive"))
    )
    (net (code "74") (name "Vbat") (class "Default")
      (node (ref "D1") (pin "1") (pinfunction "1_1") (pintype "passive"))
      (node (ref "D2") (pin "1") (pinfunction "1_1") (pintype "passive"))
      (node (ref "D3") (pin "1") (pinfunction "1_1") (pintype "passive"))
      (node (ref "D4") (pin "1") (pinfunction "1_1") (pintype "passive"))
      (node (ref "D5") (pin "1") (pinfunction "1_1") (pintype "passive"))
      (node (ref "D6") (pin "1") (pinfunction "1_1") (pintype "passive"))
      (node (ref "D7") (pin "1") (pinfunction "1_1") (pintype "passive"))
      (node (ref "D8") (pin "1") (pinfunction "1_1") (pintype "passive"))
      (node (ref "P4") (pin "13") (pinfunction "13_13") (pintype "passive"))
      (node (ref "P5") (pin "14") (pinfunction "14_14") (pintype "passive"))
      (node (ref "R2") (pin "2") (pinfunction "2_2") (pintype "passive"))
      (node (ref "U1") (pin "1") (pinfunction "IN_1") (pintype "passive"))
      (node (ref "U2") (pin "1") (pinfunction "IN_1") (pintype "passive"))
    )
    (net (code "75") (name "led0") (class "Default")
      (node (ref "U3") (pin "2") (pinfunction "PA4/ADC4/AC4_2") (pintype "passive"))
      (node (ref "U8") (pin "2") (pinfunction "G_2") (pintype "passive"))
    )
    (net (code "76") (name "led1") (class "Default")
      (node (ref "U10") (pin "2") (pinfunction "G_2") (pintype "passive"))
      (node (ref "U3") (pin "3") (pinfunction "PA5/ADC5/AC5_3") (pintype "passive"))
    )
    (net (code "77") (name "led2") (class "Default")
      (node (ref "U12") (pin "2") (pinfunction "G_2") (pintype "passive"))
      (node (ref "U3") (pin "4") (pinfunction "PA6/ADC6/AC6_4") (pintype "passive"))
    )
    (net (code "78") (name "led3") (class "Default")
      (node (ref "U14") (pin "2") (pinfunction "G_2") (pintype "passive"))
      (node (ref "U3") (pin "5") (pinfunction "PA7/ADC7/AC7_5") (pintype "passive"))
    )
    (net (code "79") (name "led4") (class "Default")
      (node (ref "U3") (pin "50") (pinfunction "PF4_50") (pintype "passive"))
      (node (ref "U7") (pin "2") (pinfunction "G_2") (pintype "passive"))
    )
    (net (code "80") (name "led5") (class "Default")
      (node (ref "U3") (pin "51") (pinfunction "PF5_51") (pintype "passive"))
      (node (ref "U9") (pin "2") (pinfunction "G_2") (pintype "passive"))
    )
    (net (code "81") (name "led6") (class "Default")
      (node (ref "U11") (pin "2") (pinfunction "G_2") (pintype "passive"))
      (node (ref "U3") (pin "54") (pinfunction "PF6_54") (pintype "passive"))
    )
    (net (code "82") (name "led7") (class "Default")
      (node (ref "U13") (pin "2") (pinfunction "G_2") (pintype "passive"))
      (node (ref "U3") (pin "55") (pinfunction "PF7_55") (pintype "passive"))
    )
    (net (code "83") (name "unconnected-(*-D0-Pad20)") (class "Default")
      (node (ref "*") (pin "20") (pinfunction "D0_20") (pintype "passive"))
    )
    (net (code "84") (name "unconnected-(*-D1-Pad19)") (class "Default")
      (node (ref "*") (pin "19") (pinfunction "D1_19") (pintype "passive"))
    )
    (net (code "85") (name "unconnected-(*-D2-Pad18)") (class "Default")
      (node (ref "*") (pin "18") (pinfunction "D2_18") (pintype "passive"))
    )
    (net (code "86") (name "unconnected-(*-D3-Pad17)") (class "Default")
      (node (ref "*") (pin "17") (pinfunction "D3_17") (pintype "passive"))
    )
    (net (code "87") (name "unconnected-(*-D4-Pad11)") (class "Default")
      (node (ref "*") (pin "11") (pinfunction "D4_11") (pintype "passive"))
    )
    (net (code "88") (name "unconnected-(*-D5-Pad15)") (class "Default")
      (node (ref "*") (pin "15") (pinfunction "D5_15") (pintype "passive"))
    )
    (net (code "89") (name "unconnected-(*-D6-Pad16)") (class "Default")
      (node (ref "*") (pin "16") (pinfunction "D6_16") (pintype "passive"))
    )
    (net (code "90") (name "unconnected-(*-D7-Pad12)") (class "Default")
      (node (ref "*") (pin "12") (pinfunction "D7_12") (pintype "passive"))
    )
    (net (code "91") (name "unconnected-(*-D8-Pad9)") (class "Default")
      (node (ref "*") (pin "9") (pinfunction "D8_9") (pintype "passive"))
    )
    (net (code "92") (name "unconnected-(*-NC-Pad4)") (class "Default")
      (node (ref "*") (pin "4") (pinfunction "NC_4") (pintype "passive"))
    )
    (net (code "93") (name "unconnected-(*-NC-Pad8)") (class "Default")
      (node (ref "*") (pin "8") (pinfunction "NC_8") (pintype "passive"))
    )
    (net (code "94") (name "unconnected-(*-P0-Pad6)") (class "Default")
      (node (ref "*") (pin "6") (pinfunction "P0_6") (pintype "passive"))
    )
    (net (code "95") (name "unconnected-(*-P1-Pad7)") (class "Default")
      (node (ref "*") (pin "7") (pinfunction "P1_7") (pintype "passive"))
    )
    (net (code "96") (name "unconnected-(*-RST-Pad5)") (class "Default")
      (node (ref "*") (pin "5") (pinfunction "RST_5") (pintype "passive"))
    )
    (net (code "97") (name "unconnected-(*-Status-Pad13)") (class "Default")
      (node (ref "*") (pin "13") (pinfunction "Status_13") (pintype "passive"))
    )
    (net (code "98") (name "unconnected-(*-VRef-Pad14)") (class "Default")
      (node (ref "*") (pin "14") (pinfunction "VRef_14") (pintype "passive"))
    )
    (net (code "99") (name "unconnected-(J1-ID-Pad4)") (class "Default")
      (node (ref "J1") (pin "4") (pinfunction "ID_4") (pintype "passive+no_connect"))
    )
    (net (code "100") (name "unconnected-(P4-Pad9)") (class "Default")
      (node (ref "P4") (pin "9") (pinfunction "9_9") (pintype "passive"))
    )
    (net (code "101") (name "unconnected-(P4-Pad11)") (class "Default")
      (node (ref "P4") (pin "11") (pinfunction "11_11") (pintype "passive"))
    )
    (net (code "102") (name "unconnected-(P5-Pad10)") (class "Default")
      (node (ref "P5") (pin "10") (pinfunction "10_10") (pintype "passive"))
    )
    (net (code "103") (name "unconnected-(P5-Pad12)") (class "Default")
      (node (ref "P5") (pin "12") (pinfunction "12_12") (pintype "passive"))
    )
    (net (code "104") (name "unconnected-(U3-PA1{slash}ADC1{slash}AC1-Pad63)") (class "Default")
      (node (ref "U3") (pin "63") (pinfunction "PA1/ADC1/AC1_63") (pintype "passive+no_connect"))
    )
    (net (code "105") (name "unconnected-(U3-PA2{slash}ADC2{slash}AC2-Pad64)") (class "Default")
      (node (ref "U3") (pin "64") (pinfunction "PA2/ADC2/AC2_64") (pintype "passive+no_connect"))
    )
    (net (code "106") (name "unconnected-(U3-PA3{slash}ADC3{slash}AC3-Pad1)") (class "Default")
      (node (ref "U3") (pin "1") (pinfunction "PA3/ADC3/AC3_1") (pintype "passive+no_connect"))
    )
    (net (code "107") (name "unconnected-(U3-PC4{slash}~{SS}-Pad20)") (class "Default")
      (node (ref "U3") (pin "20") (pinfunction "PC4/~{SS}_20") (pintype "passive"))
    )
    (net (code "108") (name "unconnected-(U3-PC5{slash}MOSI{slash}XCK1-Pad21)") (class "Default")
      (node (ref "U3") (pin "21") (pinfunction "PC5/MOSI/XCK1_21") (pintype "passive"))
    )
    (net (code "109") (name "unconnected-(U3-PD4{slash}~{SS}-Pad30)") (class "Default")
      (node (ref "U3") (pin "30") (pinfunction "PD4/~{SS}_30") (pintype "passive"))
    )
    (net (code "110") (name "unconnected-(U3-PE0{slash}SDA-Pad36)") (class "Default")
      (node (ref "U3") (pin "36") (pinfunction "PE0/SDA_36") (pintype "passive"))
    )
    (net (code "111") (name "unconnected-(U3-PE1{slash}XCK0{slash}SCL-Pad37)") (class "Default")
      (node (ref "U3") (pin "37") (pinfunction "PE1/XCK0/SCL_37") (pintype "passive"))
    )
    (net (code "112") (name "unconnected-(U3-PF0-Pad46)") (class "Default")
      (node (ref "U3") (pin "46") (pinfunction "PF0_46") (pintype "passive"))
    )
    (net (code "113") (name "unconnected-(U3-PF1{slash}XCK0-Pad47)") (class "Default")
      (node (ref "U3") (pin "47") (pinfunction "PF1/XCK0_47") (pintype "passive"))
    )
    (net (code "114") (name "unconnected-(U3-PR0{slash}XTAL2-Pad58)") (class "Default")
      (node (ref "U3") (pin "58") (pinfunction "PR0/XTAL2_58") (pintype "passive+no_connect"))
    )
    (net (code "115") (name "unconnected-(U3-PR1{slash}XTAL1-Pad59)") (class "Default")
      (node (ref "U3") (pin "59") (pinfunction "PR1/XTAL1_59") (pintype "passive+no_connect"))
    )
    (net (code "116") (name "unconnected-(U4-CTS-Pad23)") (class "Default")
      (node (ref "U4") (pin "23") (pinfunction "CTS_23") (pintype "passive+no_connect"))
    )
    (net (code "117") (name "unconnected-(U4-DCD-Pad1)") (class "Default")
      (node (ref "U4") (pin "1") (pinfunction "DCD_1") (pintype "passive+no_connect"))
    )
    (net (code "118") (name "unconnected-(U4-DSR-Pad27)") (class "Default")
      (node (ref "U4") (pin "27") (pinfunction "DSR_27") (pintype "passive+no_connect"))
    )
    (net (code "119") (name "unconnected-(U4-DTR-Pad28)") (class "Default")
      (node (ref "U4") (pin "28") (pinfunction "DTR_28") (pintype "passive+no_connect"))
    )
    (net (code "120") (name "unconnected-(U4-RI-Pad2)") (class "Default")
      (node (ref "U4") (pin "2") (pinfunction "RI_2") (pintype "passive+no_connect"))
    )
    (net (code "121") (name "unconnected-(U4-RTS-Pad24)") (class "Default")
      (node (ref "U4") (pin "24") (pinfunction "RTS_24") (pintype "passive+no_connect"))
    )
    (net (code "122") (name "unconnected-(U4-SUSPEND-Pad12)") (class "Default")
      (node (ref "U4") (pin "12") (pinfunction "SUSPEND_12") (pintype "passive+no_connect"))
    )
    (net (code "123") (name "unconnected-(U4-~{SUSPEND}-Pad11)") (class "Default")
      (node (ref "U4") (pin "11") (pinfunction "~{SUSPEND}_11") (pintype "passive+no_connect"))
    )
    (net (code "124") (name "unconnected-(U6-INVALID-Pad10)") (class "Default")
      (node (ref "U6") (pin "10") (pinfunction "INVALID_10") (pintype "passive+no_connect"))
    )
    (net (code "125") (name "usb_rx") (class "Default")
      (node (ref "U3") (pin "22") (pinfunction "PC6/MISO/RXD1_22") (pintype "passive"))
      (node (ref "U4") (pin "26") (pinfunction "TXD_26") (pintype "passive"))
    )
    (net (code "126") (name "usb_tx") (class "Default")
      (node (ref "U3") (pin "23") (pinfunction "PC7/SCK/TXD1/EVOUT_23") (pintype "passive"))
      (node (ref "U4") (pin "25") (pinfunction "RXD_25") (pintype "passive"))
    )
  )
)
